# DC_Power_Supply.net
KiCad netlist of a schematic drawn in Altium Designer
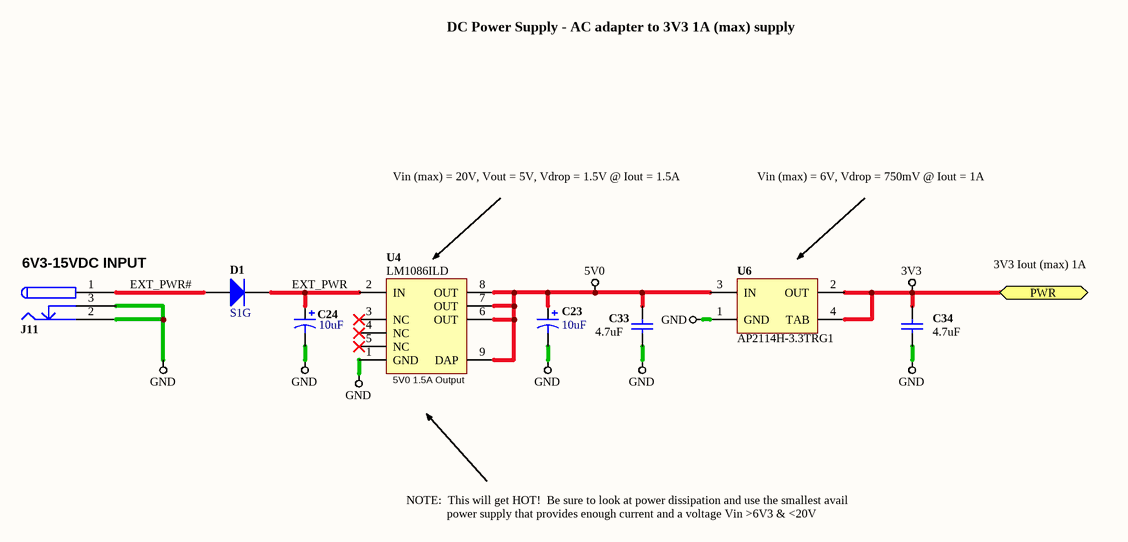
[diagram p0: DC Power Supply (AC adapter - 5V0 - 3V3).SchDoc]

(export (version "E")
  (design (tool "Eeschema 10.0.6"))
  (components
    (comp (ref "C23")
      (value "TAJB106K020R")
      (footprint "AVX-CAPC3528_V")
      (description "Capacitor, Tantalum, 10uF 10% 20V MCCT-B (3528)")
      (fields
        (field (name "CAPACITANCE") "10uF")
        (field (name "MANUFACTURER") "AVX")
        (field (name "TOLERANCE") "10%")
      )
      (libsource (lib "Altium Content Vault") (part "CMP-0279-00001-1"))
    )
    (comp (ref "C24")
      (value "TAJB106K020R")
      (footprint "AVX-CAPC3528_V")
      (description "Capacitor, Tantalum, 10uF 10% 20V MCCT-B (3528)")
      (fields
        (field (name "CAPACITANCE") "10uF")
        (field (name "MANUFACTURER") "AVX")
        (field (name "TOLERANCE") "10%")
      )
      (libsource (lib "Altium Content Vault") (part "CMP-0279-00001-1"))
    )
    (comp (ref "C33")
      (value "4.7uF")
      (footprint "CAPC0603(1608)55_L")
      (fields (field (name "TOLERANCE") "±10%") (field (name "Comment") "CAP 4.7uF 10V 0603(1608)"))
      (libsource (lib "Component_Database") (part "CAP_NP"))
    )
    (comp (ref "C34")
      (value "4.7uF")
      (footprint "CAPC0603(1608)55_L")
      (fields (field (name "TOLERANCE") "±10%") (field (name "Comment") "CAP 4.7uF 10V 0603(1608)"))
      (libsource (lib "Component_Database") (part "CAP_NP"))
    )
    (comp (ref "D1")
      (value "S1G")
      (footprint "DO-214AC")
      (description "Fairchild S1G General Purpose Rectifier")
      (libsource (lib "DIODE-S1G") (part "S1G"))
    )
    (comp (ref "J11")
      (value "PWR CONNECTOR")
      (footprint "KLD-0202")
      (description "Connector, 3 Conductor Power Jack")
      (libsource (lib "PWR_CONNECTOR_3") (part "POWER-CONNECTOR-3"))
    )
    (comp (ref "U4")
      (value "LM1086ILD-3.3/NOPB")
      (footprint "LDC08A")
      (description "1.5A Low Dropout Positive Regulators, 8-pin LLP, Pb-Free")
      (fields
        (field (name "MANUFACTURER") "National Semiconductor")
        (field (name "ABBREVIATED NAME") "LM1086ILD")
      )
      (libsource (lib "Altium Content Vault") (part "CMP-0062-01489-2"))
    )
    (comp (ref "U6")
      (value "AP2114H-3.3TRG1")
      (footprint "SOT230P700X180-4L")
      (description "AP2114, 1A Low Dropout Positive Fixed 3V3 Regulator")
      (libsource (lib "AP2114H-3.3TRG1") (part "AP2114H-3.3TRG1"))
    )
  )
  (nets
    (net (code "1") (name "/EXT_PWR") (class "Default")
      (node (ref "C24") (pin "1") (pinfunction "1_1") (pintype "passive"))
      (node (ref "D1") (pin "2") (pinfunction "2_2") (pintype "passive"))
      (node (ref "U4") (pin "2") (pinfunction "IN_2") (pintype "power_in"))
    )
    (net (code "2") (name "/EXT_PWR#") (class "Default")
      (node (ref "D1") (pin "1") (pinfunction "1_1") (pintype "passive"))
      (node (ref "J11") (pin "1") (pintype "power_in"))
    )
    (net (code "3") (name "3V3") (class "Default")
      (node (ref "C34") (pin "1") (pinfunction "1_1") (pintype "passive"))
      (node (ref "U6") (pin "2") (pinfunction "OUT_2") (pintype "power_in"))
      (node (ref "U6") (pin "4") (pinfunction "TAB_4") (pintype "power_in"))
    )
    (net (code "4") (name "5V0") (class "Default")
      (node (ref "C23") (pin "1") (pinfunction "1_1") (pintype "passive"))
      (node (ref "C33") (pin "1") (pinfunction "1_1") (pintype "passive"))
      (node (ref "U4") (pin "6") (pinfunction "OUT_6") (pintype "power_in"))
      (node (ref "U4") (pin "7") (pinfunction "OUT_7") (pintype "power_in"))
      (node (ref "U4") (pin "8") (pinfunction "OUT_8") (pintype "power_in"))
      (node (ref "U4") (pin "9") (pinfunction "DAP_9") (pintype "power_in"))
      (node (ref "U6") (pin "3") (pinfunction "IN_3") (pintype "power_in"))
    )
    (net (code "5") (name "GND") (class "Default")
      (node (ref "C23") (pin "2") (pinfunction "2_2") (pintype "passive"))
      (node (ref "C24") (pin "2") (pinfunction "2_2") (pintype "passive"))
      (node (ref "C33") (pin "2") (pinfunction "2_2") (pintype "passive"))
      (node (ref "C34") (pin "2") (pinfunction "2_2") (pintype "passive"))
      (node (ref "J11") (pin "2") (pintype "power_in"))
      (node (ref "J11") (pin "3") (pintype "power_in"))
      (node (ref "U4") (pin "1") (pinfunction "GND_1") (pintype "power_in"))
      (node (ref "U6") (pin "1") (pinfunction "GND_1") (pintype "power_in"))
    )
    (net (code "6") (name "unconnected-(U4-NC-Pad3)") (class "Default")
      (node (ref "U4") (pin "3") (pinfunction "NC_3") (pintype "passive+no_connect"))
    )
    (net (code "7") (name "unconnected-(U4-NC-Pad4)") (class "Default")
      (node (ref "U4") (pin "4") (pinfunction "NC_4") (pintype "passive+no_connect"))
    )
    (net (code "8") (name "unconnected-(U4-NC-Pad5)") (class "Default")
      (node (ref "U4") (pin "5") (pinfunction "NC_5") (pintype "passive+no_connect"))
    )
  )
)
